# X7Segment.net
KiCad netlist of a schematic drawn in EAGLE
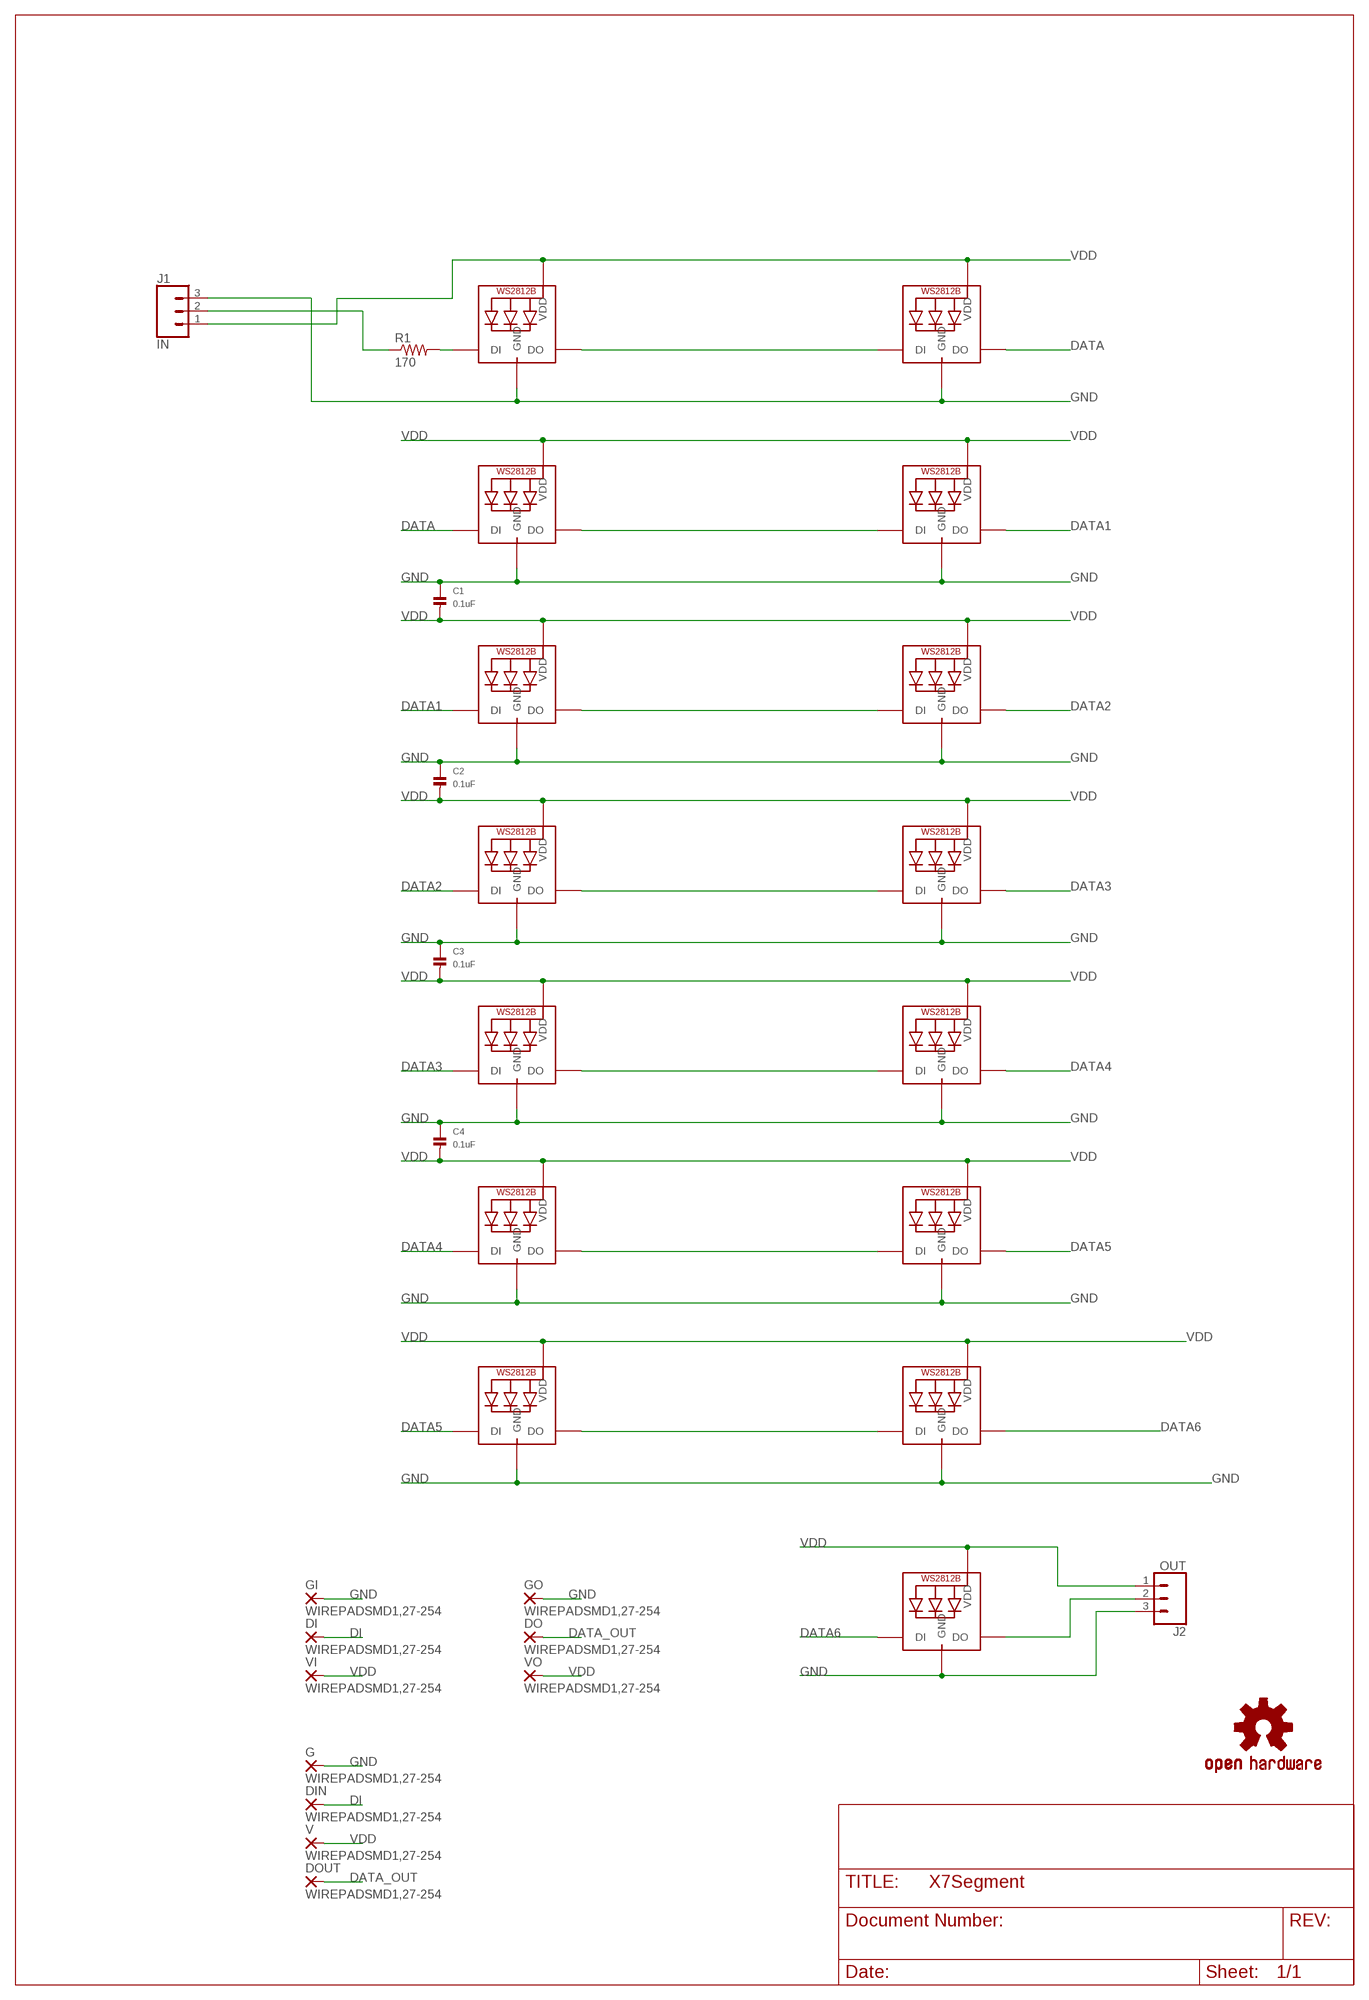
[diagram p0: schematic, sheet 1]

(export (version "E")
  (design (tool "Eeschema 10.0.6"))
  (components
    (comp (ref "C1")
      (value "0.1uF")
      (footprint "eagle-import:_0603MP")
      (libsource (lib "eagle-import") (part "CAP_CERAMIC_0603MP"))
    )
    (comp (ref "C2")
      (value "0.1uF")
      (footprint "eagle-import:_0603MP")
      (libsource (lib "eagle-import") (part "CAP_CERAMIC_0603MP"))
    )
    (comp (ref "C3")
      (value "0.1uF")
      (footprint "eagle-import:_0603MP")
      (libsource (lib "eagle-import") (part "CAP_CERAMIC_0603MP"))
    )
    (comp (ref "C4")
      (value "0.1uF")
      (footprint "eagle-import:_0603MP")
      (libsource (lib "eagle-import") (part "CAP_CERAMIC_0603MP"))
    )
    (comp (ref "DI")
      (value "WIREPADSMD1,27-254")
      (footprint "eagle-import:SMD1,27-2,54")
      (libsource (lib "eagle-import") (part "WIREPADSMD1,27-254"))
    )
    (comp (ref "DIN")
      (value "WIREPADSMD1,27-254")
      (footprint "eagle-import:SMD1,27-2,54")
      (libsource (lib "eagle-import") (part "WIREPADSMD1,27-254"))
    )
    (comp (ref "DO")
      (value "WIREPADSMD1,27-254")
      (footprint "eagle-import:SMD1,27-2,54")
      (libsource (lib "eagle-import") (part "WIREPADSMD1,27-254"))
    )
    (comp (ref "DOUT")
      (value "WIREPADSMD1,27-254")
      (footprint "eagle-import:SMD1,27-2,54")
      (libsource (lib "eagle-import") (part "WIREPADSMD1,27-254"))
    )
    (comp (ref "G")
      (value "WIREPADSMD1,27-254")
      (footprint "eagle-import:SMD1,27-2,54")
      (libsource (lib "eagle-import") (part "WIREPADSMD1,27-254"))
    )
    (comp (ref "GI")
      (value "WIREPADSMD1,27-254")
      (footprint "eagle-import:SMD1,27-2,54")
      (libsource (lib "eagle-import") (part "WIREPADSMD1,27-254"))
    )
    (comp (ref "GO")
      (value "WIREPADSMD1,27-254")
      (footprint "eagle-import:SMD1,27-2,54")
      (libsource (lib "eagle-import") (part "WIREPADSMD1,27-254"))
    )
    (comp (ref "J1")
      (value "IN")
      (footprint "eagle-import:1X03_NO_SILK")
      (libsource (lib "eagle-import") (part "CONN_031X03_NO_SILK"))
    )
    (comp (ref "J2")
      (value "OUT")
      (footprint "eagle-import:1X03_NO_SILK")
      (libsource (lib "eagle-import") (part "CONN_031X03_NO_SILK"))
    )
    (comp (ref "LED1")
      (value "WS2812B4020_SIDEWAYS")
      (footprint "eagle-import:4020_SIDEWAYS")
      (libsource (lib "eagle-import") (part "WS2812B4020_SIDEWAYS"))
    )
    (comp (ref "LED4")
      (value "WS2812B4020_SIDEWAYS")
      (footprint "eagle-import:4020_SIDEWAYS")
      (libsource (lib "eagle-import") (part "WS2812B4020_SIDEWAYS"))
    )
    (comp (ref "LED5")
      (value "WS2812B4020_SIDEWAYS")
      (footprint "eagle-import:4020_SIDEWAYS")
      (libsource (lib "eagle-import") (part "WS2812B4020_SIDEWAYS"))
    )
    (comp (ref "LED8")
      (value "WS2812B4020_SIDEWAYS")
      (footprint "eagle-import:4020_SIDEWAYS")
      (libsource (lib "eagle-import") (part "WS2812B4020_SIDEWAYS"))
    )
    (comp (ref "LED9")
      (value "WS2812B4020_SIDEWAYS")
      (footprint "eagle-import:4020_SIDEWAYS")
      (libsource (lib "eagle-import") (part "WS2812B4020_SIDEWAYS"))
    )
    (comp (ref "LED12")
      (value "WS2812B4020_SIDEWAYS")
      (footprint "eagle-import:4020_SIDEWAYS")
      (libsource (lib "eagle-import") (part "WS2812B4020_SIDEWAYS"))
    )
    (comp (ref "LED13")
      (value "WS2812B4020_SIDEWAYS")
      (footprint "eagle-import:4020_SIDEWAYS")
      (libsource (lib "eagle-import") (part "WS2812B4020_SIDEWAYS"))
    )
    (comp (ref "LED16")
      (value "WS2812B4020_SIDEWAYS")
      (footprint "eagle-import:4020_SIDEWAYS")
      (libsource (lib "eagle-import") (part "WS2812B4020_SIDEWAYS"))
    )
    (comp (ref "LED17")
      (value "WS2812B4020_SIDEWAYS")
      (footprint "eagle-import:4020_SIDEWAYS")
      (libsource (lib "eagle-import") (part "WS2812B4020_SIDEWAYS"))
    )
    (comp (ref "LED20")
      (value "WS2812B4020_SIDEWAYS")
      (footprint "eagle-import:4020_SIDEWAYS")
      (libsource (lib "eagle-import") (part "WS2812B4020_SIDEWAYS"))
    )
    (comp (ref "LED21")
      (value "WS2812B4020_SIDEWAYS")
      (footprint "eagle-import:4020_SIDEWAYS")
      (libsource (lib "eagle-import") (part "WS2812B4020_SIDEWAYS"))
    )
    (comp (ref "LED24")
      (value "WS2812B4020_SIDEWAYS")
      (footprint "eagle-import:4020_SIDEWAYS")
      (libsource (lib "eagle-import") (part "WS2812B4020_SIDEWAYS"))
    )
    (comp (ref "LED25")
      (value "WS2812B4020_SIDEWAYS")
      (footprint "eagle-import:4020_SIDEWAYS")
      (libsource (lib "eagle-import") (part "WS2812B4020_SIDEWAYS"))
    )
    (comp (ref "LED28")
      (value "WS2812B4020_SIDEWAYS")
      (footprint "eagle-import:4020_SIDEWAYS")
      (libsource (lib "eagle-import") (part "WS2812B4020_SIDEWAYS"))
    )
    (comp (ref "LED29")
      (value "RGB 3535")
      (footprint "eagle-import:LED3535")
      (libsource (lib "eagle-import") (part "adafruit_WS2812B3535"))
    )
    (comp (ref "LOGO1")
      (value "OSHW-LOGOS")
      (footprint "eagle-import:OSHW-LOGO-S")
      (libsource (lib "eagle-import") (part "OSHW-LOGOS"))
    )
    (comp (ref "R1")
      (value "170")
      (footprint "eagle-import:R0805")
      (libsource (lib "eagle-import") (part "R-US_R0805"))
    )
    (comp (ref "V")
      (value "WIREPADSMD1,27-254")
      (footprint "eagle-import:SMD1,27-2,54")
      (libsource (lib "eagle-import") (part "WIREPADSMD1,27-254"))
    )
    (comp (ref "VI")
      (value "WIREPADSMD1,27-254")
      (footprint "eagle-import:SMD1,27-2,54")
      (libsource (lib "eagle-import") (part "WIREPADSMD1,27-254"))
    )
    (comp (ref "VO")
      (value "WIREPADSMD1,27-254")
      (footprint "eagle-import:SMD1,27-2,54")
      (libsource (lib "eagle-import") (part "WIREPADSMD1,27-254"))
    )
  )
  (nets
    (net (code "1") (name "/DATA") (class "Default")
      (node (ref "LED4") (pin "2-DOUT") (pinfunction "DO_2-DOUT") (pintype "output"))
      (node (ref "LED5") (pin "4-DIN") (pinfunction "DI_4-DIN") (pintype "input"))
    )
    (net (code "2") (name "/DATA1") (class "Default")
      (node (ref "LED8") (pin "2-DOUT") (pinfunction "DO_2-DOUT") (pintype "output"))
      (node (ref "LED9") (pin "4-DIN") (pinfunction "DI_4-DIN") (pintype "input"))
    )
    (net (code "3") (name "/DATA2") (class "Default")
      (node (ref "LED12") (pin "2-DOUT") (pinfunction "DO_2-DOUT") (pintype "output"))
      (node (ref "LED13") (pin "4-DIN") (pinfunction "DI_4-DIN") (pintype "input"))
    )
    (net (code "4") (name "/DATA3") (class "Default")
      (node (ref "LED16") (pin "2-DOUT") (pinfunction "DO_2-DOUT") (pintype "output"))
      (node (ref "LED17") (pin "4-DIN") (pinfunction "DI_4-DIN") (pintype "input"))
    )
    (net (code "5") (name "/DATA4") (class "Default")
      (node (ref "LED20") (pin "2-DOUT") (pinfunction "DO_2-DOUT") (pintype "output"))
      (node (ref "LED21") (pin "4-DIN") (pinfunction "DI_4-DIN") (pintype "input"))
    )
    (net (code "6") (name "/DATA5") (class "Default")
      (node (ref "LED24") (pin "2-DOUT") (pinfunction "DO_2-DOUT") (pintype "output"))
      (node (ref "LED25") (pin "4-DIN") (pinfunction "DI_4-DIN") (pintype "input"))
    )
    (net (code "7") (name "/DATA6") (class "Default")
      (node (ref "LED28") (pin "2-DOUT") (pinfunction "DO_2-DOUT") (pintype "output"))
      (node (ref "LED29") (pin "1") (pinfunction "DI_1") (pintype "input"))
    )
    (net (code "8") (name "/DATA_OUT") (class "Default")
      (node (ref "DO") (pin "1") (pinfunction "P_1") (pintype "passive"))
      (node (ref "DOUT") (pin "1") (pinfunction "P_1") (pintype "passive"))
      (node (ref "J2") (pin "2") (pinfunction "2_2") (pintype "passive"))
      (node (ref "LED29") (pin "3") (pinfunction "DO_3") (pintype "output"))
    )
    (net (code "9") (name "/DI") (class "Default")
      (node (ref "DI") (pin "1") (pinfunction "P_1") (pintype "passive"))
      (node (ref "DIN") (pin "1") (pinfunction "P_1") (pintype "passive"))
      (node (ref "J1") (pin "2") (pinfunction "2_2") (pintype "passive"))
      (node (ref "R1") (pin "1") (pinfunction "1_1") (pintype "passive"))
    )
    (net (code "10") (name "/GND") (class "Default")
      (node (ref "C1") (pin "1") (pinfunction "P$1_1") (pintype "passive"))
      (node (ref "C2") (pin "1") (pinfunction "P$1_1") (pintype "passive"))
      (node (ref "C3") (pin "1") (pinfunction "P$1_1") (pintype "passive"))
      (node (ref "C4") (pin "1") (pinfunction "P$1_1") (pintype "passive"))
      (node (ref "G") (pin "1") (pinfunction "P_1") (pintype "passive"))
      (node (ref "GI") (pin "1") (pinfunction "P_1") (pintype "passive"))
      (node (ref "GO") (pin "1") (pinfunction "P_1") (pintype "passive"))
      (node (ref "J1") (pin "3") (pinfunction "3_3") (pintype "passive"))
      (node (ref "J2") (pin "3") (pinfunction "3_3") (pintype "passive"))
      (node (ref "LED1") (pin "3-GND") (pinfunction "GND_3-GND") (pintype "power_in"))
      (node (ref "LED12") (pin "3-GND") (pinfunction "GND_3-GND") (pintype "power_in"))
      (node (ref "LED13") (pin "3-GND") (pinfunction "GND_3-GND") (pintype "power_in"))
      (node (ref "LED16") (pin "3-GND") (pinfunction "GND_3-GND") (pintype "power_in"))
      (node (ref "LED17") (pin "3-GND") (pinfunction "GND_3-GND") (pintype "power_in"))
      (node (ref "LED20") (pin "3-GND") (pinfunction "GND_3-GND") (pintype "power_in"))
      (node (ref "LED21") (pin "3-GND") (pinfunction "GND_3-GND") (pintype "power_in"))
      (node (ref "LED24") (pin "3-GND") (pinfunction "GND_3-GND") (pintype "power_in"))
      (node (ref "LED25") (pin "3-GND") (pinfunction "GND_3-GND") (pintype "power_in"))
      (node (ref "LED28") (pin "3-GND") (pinfunction "GND_3-GND") (pintype "power_in"))
      (node (ref "LED29") (pin "4") (pinfunction "GND_4") (pintype "power_in"))
      (node (ref "LED4") (pin "3-GND") (pinfunction "GND_3-GND") (pintype "power_in"))
      (node (ref "LED5") (pin "3-GND") (pinfunction "GND_3-GND") (pintype "power_in"))
      (node (ref "LED8") (pin "3-GND") (pinfunction "GND_3-GND") (pintype "power_in"))
      (node (ref "LED9") (pin "3-GND") (pinfunction "GND_3-GND") (pintype "power_in"))
    )
    (net (code "11") (name "/VDD") (class "Default")
      (node (ref "C1") (pin "2") (pinfunction "P$2_2") (pintype "passive"))
      (node (ref "C2") (pin "2") (pinfunction "P$2_2") (pintype "passive"))
      (node (ref "C3") (pin "2") (pinfunction "P$2_2") (pintype "passive"))
      (node (ref "C4") (pin "2") (pinfunction "P$2_2") (pintype "passive"))
      (node (ref "J1") (pin "1") (pinfunction "1_1") (pintype "passive"))
      (node (ref "J2") (pin "1") (pinfunction "1_1") (pintype "passive"))
      (node (ref "LED1") (pin "1-VDD") (pinfunction "VDD_1-VDD") (pintype "power_in"))
      (node (ref "LED12") (pin "1-VDD") (pinfunction "VDD_1-VDD") (pintype "power_in"))
      (node (ref "LED13") (pin "1-VDD") (pinfunction "VDD_1-VDD") (pintype "power_in"))
      (node (ref "LED16") (pin "1-VDD") (pinfunction "VDD_1-VDD") (pintype "power_in"))
      (node (ref "LED17") (pin "1-VDD") (pinfunction "VDD_1-VDD") (pintype "power_in"))
      (node (ref "LED20") (pin "1-VDD") (pinfunction "VDD_1-VDD") (pintype "power_in"))
      (node (ref "LED21") (pin "1-VDD") (pinfunction "VDD_1-VDD") (pintype "power_in"))
      (node (ref "LED24") (pin "1-VDD") (pinfunction "VDD_1-VDD") (pintype "power_in"))
      (node (ref "LED25") (pin "1-VDD") (pinfunction "VDD_1-VDD") (pintype "power_in"))
      (node (ref "LED28") (pin "1-VDD") (pinfunction "VDD_1-VDD") (pintype "power_in"))
      (node (ref "LED29") (pin "2") (pinfunction "VDD_2") (pintype "power_in"))
      (node (ref "LED4") (pin "1-VDD") (pinfunction "VDD_1-VDD") (pintype "power_in"))
      (node (ref "LED5") (pin "1-VDD") (pinfunction "VDD_1-VDD") (pintype "power_in"))
      (node (ref "LED8") (pin "1-VDD") (pinfunction "VDD_1-VDD") (pintype "power_in"))
      (node (ref "LED9") (pin "1-VDD") (pinfunction "VDD_1-VDD") (pintype "power_in"))
      (node (ref "V") (pin "1") (pinfunction "P_1") (pintype "passive"))
      (node (ref "VI") (pin "1") (pinfunction "P_1") (pintype "passive"))
      (node (ref "VO") (pin "1") (pinfunction "P_1") (pintype "passive"))
    )
    (net (code "12") (name "Net-(LED1-DI)") (class "Default")
      (node (ref "LED1") (pin "4-DIN") (pinfunction "DI_4-DIN") (pintype "input"))
      (node (ref "R1") (pin "2") (pinfunction "2_2") (pintype "passive"))
    )
    (net (code "13") (name "Net-(LED1-DO)") (class "Default")
      (node (ref "LED1") (pin "2-DOUT") (pinfunction "DO_2-DOUT") (pintype "output"))
      (node (ref "LED4") (pin "4-DIN") (pinfunction "DI_4-DIN") (pintype "input"))
    )
    (net (code "14") (name "Net-(LED5-DO)") (class "Default")
      (node (ref "LED5") (pin "2-DOUT") (pinfunction "DO_2-DOUT") (pintype "output"))
      (node (ref "LED8") (pin "4-DIN") (pinfunction "DI_4-DIN") (pintype "input"))
    )
    (net (code "15") (name "Net-(LED12-DI)") (class "Default")
      (node (ref "LED12") (pin "4-DIN") (pinfunction "DI_4-DIN") (pintype "input"))
      (node (ref "LED9") (pin "2-DOUT") (pinfunction "DO_2-DOUT") (pintype "output"))
    )
    (net (code "16") (name "Net-(LED13-DO)") (class "Default")
      (node (ref "LED13") (pin "2-DOUT") (pinfunction "DO_2-DOUT") (pintype "output"))
      (node (ref "LED16") (pin "4-DIN") (pinfunction "DI_4-DIN") (pintype "input"))
    )
    (net (code "17") (name "Net-(LED17-DO)") (class "Default")
      (node (ref "LED17") (pin "2-DOUT") (pinfunction "DO_2-DOUT") (pintype "output"))
      (node (ref "LED20") (pin "4-DIN") (pinfunction "DI_4-DIN") (pintype "input"))
    )
    (net (code "18") (name "Net-(LED21-DO)") (class "Default")
      (node (ref "LED21") (pin "2-DOUT") (pinfunction "DO_2-DOUT") (pintype "output"))
      (node (ref "LED24") (pin "4-DIN") (pinfunction "DI_4-DIN") (pintype "input"))
    )
    (net (code "19") (name "Net-(LED25-DO)") (class "Default")
      (node (ref "LED25") (pin "2-DOUT") (pinfunction "DO_2-DOUT") (pintype "output"))
      (node (ref "LED28") (pin "4-DIN") (pinfunction "DI_4-DIN") (pintype "input"))
    )
  )
)
